# SK3000v5_LOGO.net
KiCad netlist of a schematic drawn in EAGLE
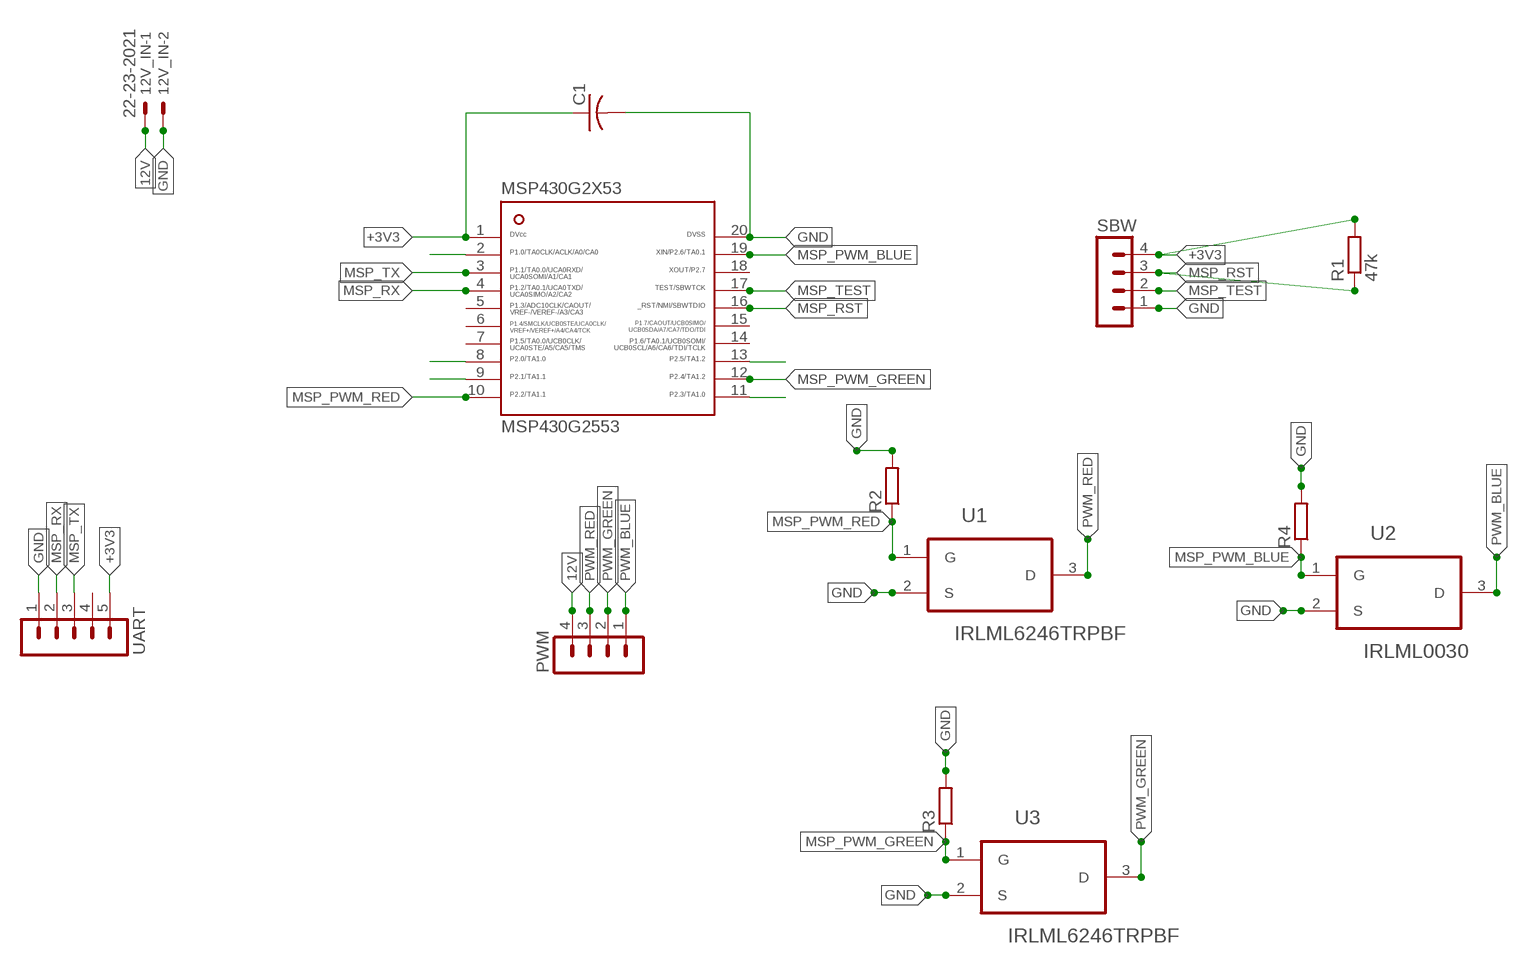
[diagram p0: schematic, sheet 1]

(export (version "E")
  (design (tool "Eeschema 10.0.6"))
  (components
    (comp (ref "12V_IN")
      (value "22-23-2021")
      (footprint "eagle-import:22-23-2021")
      (fields (field (name "MF") "MOLEX"))
      (libsource (lib "eagle-import") (part "22-23-2021"))
    )
    (comp (ref "C1")
      (value "C-USC0603")
      (footprint "eagle-import:C0603")
      (libsource (lib "eagle-import") (part "C-USC0603"))
    )
    (comp (ref "MSP430G2553")
      (value "MSP430G2X53-20PW20")
      (footprint "eagle-import:PW20")
      (libsource (lib "eagle-import") (part "MSP430G2X53-20PW20"))
    )
    (comp (ref "PWM")
      (value "MA04-1")
      (footprint "eagle-import:MA04-1")
      (libsource (lib "eagle-import") (part "MA04-1"))
    )
    (comp (ref "R1")
      (value "47k")
      (footprint "eagle-import:R0603")
      (libsource (lib "eagle-import") (part "R-EU_R0603"))
    )
    (comp (ref "R2")
      (value "R-EU_R0603")
      (footprint "eagle-import:R0603")
      (libsource (lib "eagle-import") (part "R-EU_R0603"))
    )
    (comp (ref "R3")
      (value "R-EU_R0603")
      (footprint "eagle-import:R0603")
      (libsource (lib "eagle-import") (part "R-EU_R0603"))
    )
    (comp (ref "R4")
      (value "R-EU_R0603")
      (footprint "eagle-import:R0603")
      (libsource (lib "eagle-import") (part "R-EU_R0603"))
    )
    (comp (ref "SBW")
      (value "MA04-1")
      (footprint "eagle-import:MA04-1")
      (libsource (lib "eagle-import") (part "MA04-1"))
    )
    (comp (ref "U1")
      (value "IRLML6246TRPBF")
      (footprint "eagle-import:SOT95P240X112-3N")
      (libsource (lib "eagle-import") (part "IRLML6246TRPBF"))
    )
    (comp (ref "U2")
      (value "IRLML0030")
      (footprint "eagle-import:SOT95P240X112-3N")
      (fields (field (name "MPN") "IRLML6246TRPBF"))
      (libsource (lib "eagle-import") (part "IRLML6246TRPBF"))
    )
    (comp (ref "U3")
      (value "IRLML6246TRPBF")
      (footprint "eagle-import:SOT95P240X112-3N")
      (libsource (lib "eagle-import") (part "IRLML6246TRPBF"))
    )
    (comp (ref "UART")
      (value "MA05-1")
      (footprint "eagle-import:MA05-1")
      (libsource (lib "eagle-import") (part "MA05-1"))
    )
  )
  (nets
    (net (code "1") (name "+3V3") (class "Default")
      (node (ref "C1") (pin "1") (pinfunction "1_1") (pintype "passive"))
      (node (ref "MSP430G2553") (pin "1") (pinfunction "1_1") (pintype "bidirectional"))
      (node (ref "R1") (pin "2") (pinfunction "2_2") (pintype "passive"))
      (node (ref "SBW") (pin "4") (pinfunction "4_4") (pintype "passive"))
      (node (ref "UART") (pin "5") (pinfunction "5_5") (pintype "passive"))
    )
    (net (code "2") (name "12V") (class "Default")
      (node (ref "12V_IN") (pin "1") (pinfunction "S_1") (pintype "passive"))
      (node (ref "PWM") (pin "4") (pinfunction "4_4") (pintype "passive"))
    )
    (net (code "3") (name "GND") (class "Default")
      (node (ref "12V_IN") (pin "2") (pinfunction "S_2") (pintype "passive"))
      (node (ref "C1") (pin "2") (pinfunction "2_2") (pintype "passive"))
      (node (ref "MSP430G2553") (pin "20") (pinfunction "20_20") (pintype "bidirectional"))
      (node (ref "R2") (pin "2") (pinfunction "2_2") (pintype "passive"))
      (node (ref "R3") (pin "2") (pinfunction "2_2") (pintype "passive"))
      (node (ref "R4") (pin "2") (pinfunction "2_2") (pintype "passive"))
      (node (ref "SBW") (pin "1") (pinfunction "1_1") (pintype "passive"))
      (node (ref "U1") (pin "2") (pinfunction "S_2") (pintype "passive"))
      (node (ref "U2") (pin "2") (pinfunction "S_2") (pintype "passive"))
      (node (ref "U3") (pin "2") (pinfunction "S_2") (pintype "passive"))
      (node (ref "UART") (pin "1") (pinfunction "1_1") (pintype "passive"))
    )
    (net (code "4") (name "MSP_PWM_BLUE") (class "Default")
      (node (ref "MSP430G2553") (pin "19") (pinfunction "19_19") (pintype "bidirectional"))
      (node (ref "R4") (pin "1") (pinfunction "1_1") (pintype "passive"))
      (node (ref "U2") (pin "1") (pinfunction "G_1") (pintype "input"))
    )
    (net (code "5") (name "MSP_PWM_GREEN") (class "Default")
      (node (ref "MSP430G2553") (pin "12") (pinfunction "12_12") (pintype "bidirectional"))
      (node (ref "R3") (pin "1") (pinfunction "1_1") (pintype "passive"))
      (node (ref "U3") (pin "1") (pinfunction "G_1") (pintype "input"))
    )
    (net (code "6") (name "MSP_PWM_RED") (class "Default")
      (node (ref "MSP430G2553") (pin "10") (pinfunction "10_10") (pintype "bidirectional"))
      (node (ref "R2") (pin "1") (pinfunction "1_1") (pintype "passive"))
      (node (ref "U1") (pin "1") (pinfunction "G_1") (pintype "input"))
    )
    (net (code "7") (name "MSP_RST") (class "Default")
      (node (ref "MSP430G2553") (pin "16") (pinfunction "16_16") (pintype "bidirectional"))
      (node (ref "R1") (pin "1") (pinfunction "1_1") (pintype "passive"))
      (node (ref "SBW") (pin "3") (pinfunction "3_3") (pintype "passive"))
    )
    (net (code "8") (name "MSP_RX") (class "Default")
      (node (ref "MSP430G2553") (pin "4") (pinfunction "4_4") (pintype "bidirectional"))
      (node (ref "UART") (pin "2") (pinfunction "2_2") (pintype "passive"))
    )
    (net (code "9") (name "MSP_TEST") (class "Default")
      (node (ref "MSP430G2553") (pin "17") (pinfunction "17_17") (pintype "bidirectional"))
      (node (ref "SBW") (pin "2") (pinfunction "2_2") (pintype "passive"))
    )
    (net (code "10") (name "MSP_TX") (class "Default")
      (node (ref "MSP430G2553") (pin "3") (pinfunction "3_3") (pintype "bidirectional"))
      (node (ref "UART") (pin "3") (pinfunction "3_3") (pintype "passive"))
    )
    (net (code "11") (name "PWM_BLUE") (class "Default")
      (node (ref "PWM") (pin "1") (pinfunction "1_1") (pintype "passive"))
      (node (ref "U2") (pin "3") (pinfunction "D_3") (pintype "output"))
    )
    (net (code "12") (name "PWM_GREEN") (class "Default")
      (node (ref "PWM") (pin "2") (pinfunction "2_2") (pintype "passive"))
      (node (ref "U3") (pin "3") (pinfunction "D_3") (pintype "output"))
    )
    (net (code "13") (name "PWM_RED") (class "Default")
      (node (ref "PWM") (pin "3") (pinfunction "3_3") (pintype "passive"))
      (node (ref "U1") (pin "3") (pinfunction "D_3") (pintype "output"))
    )
    (net (code "14") (name "unconnected-(MSP430G2553-Pad2)") (class "Default")
      (node (ref "MSP430G2553") (pin "2") (pinfunction "2_2") (pintype "bidirectional"))
    )
    (net (code "15") (name "unconnected-(MSP430G2553-Pad5)") (class "Default")
      (node (ref "MSP430G2553") (pin "5") (pinfunction "5_5") (pintype "bidirectional"))
    )
    (net (code "16") (name "unconnected-(MSP430G2553-Pad6)") (class "Default")
      (node (ref "MSP430G2553") (pin "6") (pinfunction "6_6") (pintype "bidirectional"))
    )
    (net (code "17") (name "unconnected-(MSP430G2553-Pad7)") (class "Default")
      (node (ref "MSP430G2553") (pin "7") (pinfunction "7_7") (pintype "bidirectional"))
    )
    (net (code "18") (name "unconnected-(MSP430G2553-Pad8)") (class "Default")
      (node (ref "MSP430G2553") (pin "8") (pinfunction "8_8") (pintype "bidirectional"))
    )
    (net (code "19") (name "unconnected-(MSP430G2553-Pad9)") (class "Default")
      (node (ref "MSP430G2553") (pin "9") (pinfunction "9_9") (pintype "bidirectional"))
    )
    (net (code "20") (name "unconnected-(MSP430G2553-Pad11)") (class "Default")
      (node (ref "MSP430G2553") (pin "11") (pinfunction "11_11") (pintype "bidirectional"))
    )
    (net (code "21") (name "unconnected-(MSP430G2553-Pad13)") (class "Default")
      (node (ref "MSP430G2553") (pin "13") (pinfunction "13_13") (pintype "bidirectional"))
    )
    (net (code "22") (name "unconnected-(MSP430G2553-Pad14)") (class "Default")
      (node (ref "MSP430G2553") (pin "14") (pinfunction "14_14") (pintype "bidirectional"))
    )
    (net (code "23") (name "unconnected-(MSP430G2553-Pad15)") (class "Default")
      (node (ref "MSP430G2553") (pin "15") (pinfunction "15_15") (pintype "bidirectional"))
    )
    (net (code "24") (name "unconnected-(MSP430G2553-Pad18)") (class "Default")
      (node (ref "MSP430G2553") (pin "18") (pinfunction "18_18") (pintype "bidirectional"))
    )
    (net (code "25") (name "unconnected-(UART-Pad4)") (class "Default")
      (node (ref "UART") (pin "4") (pinfunction "4_4") (pintype "passive"))
    )
  )
)
